# ts.net
KiCad netlist of a schematic drawn in Altium Designer
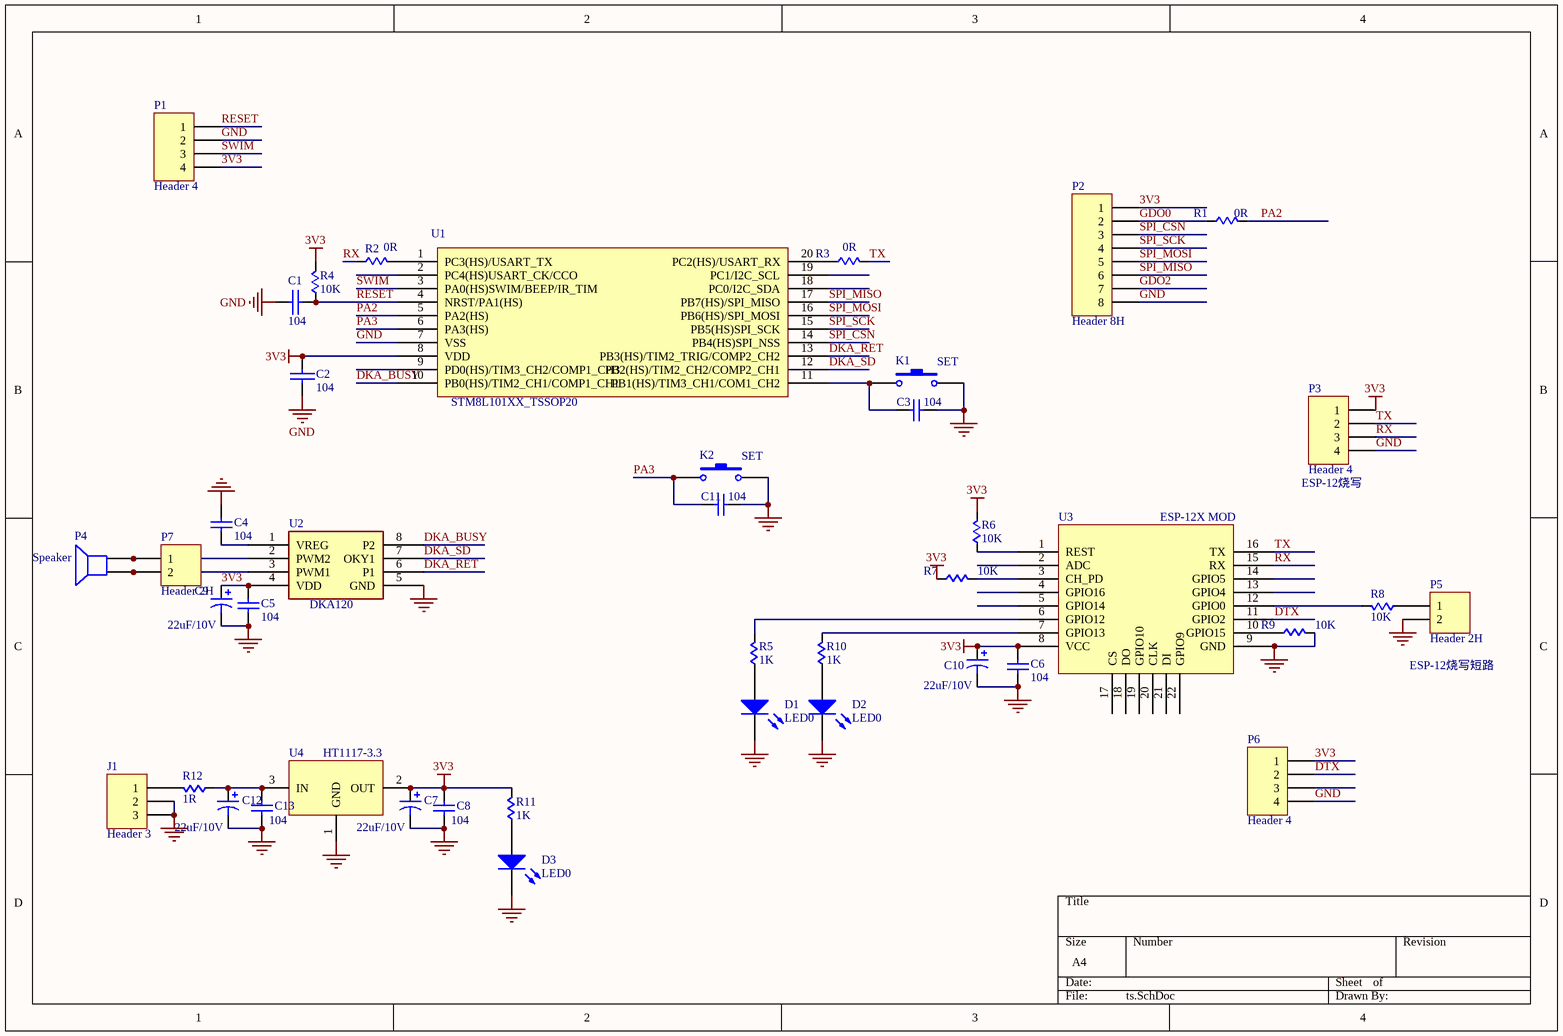
[diagram p0: ts.SchDoc]

(export (version "E")
  (design (tool "Eeschema 10.0.6"))
  (components
    (comp (ref "C1")
      (value "104")
      (footprint "0603")
      (description "Capacitor")
      (libsource (lib "*") (part "CAP"))
    )
    (comp (ref "C2")
      (value "104")
      (footprint "0603")
      (description "Capacitor")
      (libsource (lib "") (part "CAP_1"))
    )
    (comp (ref "C3")
      (value "104")
      (footprint "0603")
      (description "Capacitor (Semiconductor SIM Model)")
      (fields (field (name "PUBLISHER") "Altium Limited"))
      (libsource (lib "") (part "Cap Semi_1"))
    )
    (comp (ref "C4")
      (value "104")
      (footprint "0603")
      (description "Capacitor (Semiconductor SIM Model)")
      (fields (field (name "PUBLISHER") "Altium Limited"))
      (libsource (lib "Miscellaneous Devices") (part "Cap Semi"))
    )
    (comp (ref "C5")
      (value "104")
      (footprint "0603")
      (description "Capacitor (Semiconductor SIM Model)")
      (fields (field (name "PUBLISHER") "Altium Limited"))
      (libsource (lib "Miscellaneous Devices") (part "Cap Semi"))
    )
    (comp (ref "C6")
      (value "104")
      (footprint "0603")
      (description "Capacitor (Semiconductor SIM Model)")
      (fields (field (name "PUBLISHER") "Altium Limited"))
      (libsource (lib "Miscellaneous Devices") (part "Cap Semi"))
    )
    (comp (ref "C7")
      (value "22uF/10V")
      (footprint "T3528")
      (description "Polarized Capacitor (Surface Mount)")
      (fields (field (name "Comment") "20uF/10V") (field (name "PUBLISHER") "Altium Limited"))
      (libsource (lib "Miscellaneous Devices") (part "Cap Pol3"))
    )
    (comp (ref "C8")
      (value "104")
      (footprint "0603")
      (description "Capacitor (Semiconductor SIM Model)")
      (fields (field (name "PUBLISHER") "Altium Limited"))
      (libsource (lib "Miscellaneous Devices") (part "Cap Semi"))
    )
    (comp (ref "C9")
      (value "22uF/10V")
      (footprint "T3528")
      (description "Polarized Capacitor (Surface Mount)")
      (fields (field (name "Comment") "20uF/10V") (field (name "PUBLISHER") "Altium Limited"))
      (libsource (lib "Miscellaneous Devices") (part "Cap Pol3"))
    )
    (comp (ref "C10")
      (value "22uF/10V")
      (footprint "T3528")
      (description "Polarized Capacitor (Surface Mount)")
      (fields (field (name "Comment") "20uF/10V") (field (name "PUBLISHER") "Altium Limited"))
      (libsource (lib "Miscellaneous Devices") (part "Cap Pol3"))
    )
    (comp (ref "C11")
      (value "104")
      (footprint "0603")
      (description "Capacitor (Semiconductor SIM Model)")
      (fields (field (name "PUBLISHER") "Altium Limited"))
      (libsource (lib "") (part "Cap Semi_1"))
    )
    (comp (ref "C12")
      (value "22uF/10V")
      (footprint "T3528")
      (description "Polarized Capacitor (Surface Mount)")
      (fields (field (name "Comment") "20uF/10V") (field (name "PUBLISHER") "Altium Limited"))
      (libsource (lib "Miscellaneous Devices") (part "Cap Pol3"))
    )
    (comp (ref "C13")
      (value "104")
      (footprint "0603")
      (description "Capacitor (Semiconductor SIM Model)")
      (fields (field (name "PUBLISHER") "Altium Limited"))
      (libsource (lib "Miscellaneous Devices") (part "Cap Semi"))
    )
    (comp (ref "D1")
      (value "LED0")
      (footprint "LED2")
      (description "Typical INFRARED GaAs LED")
      (fields (field (name "PUBLISHER") "Altium Limited"))
      (libsource (lib "Miscellaneous Devices") (part "LED0"))
    )
    (comp (ref "D2")
      (value "LED0")
      (footprint "LED2")
      (description "Typical INFRARED GaAs LED")
      (fields (field (name "PUBLISHER") "Altium Limited"))
      (libsource (lib "Miscellaneous Devices") (part "LED0"))
    )
    (comp (ref "D3")
      (value "LED0")
      (footprint "LED2")
      (description "Typical INFRARED GaAs LED")
      (fields (field (name "PUBLISHER") "Altium Limited"))
      (libsource (lib "Miscellaneous Devices") (part "LED0"))
    )
    (comp (ref "J1")
      (value "Header 3")
      (footprint "DC3.5")
      (description "Header, 3-Pin")
      (fields (field (name "PUBLISHER") "Altium Limited"))
      (libsource (lib "Miscellaneous Connectors") (part "Header 3"))
    )
    (comp (ref "K1")
      (value "SET")
      (footprint "KEY_1")
      (description "Switch")
      (fields (field (name "PUBLISHER") "Altium Limited"))
      (libsource (lib "Miscellaneous Devices") (part "SW-PB"))
    )
    (comp (ref "K2")
      (value "SET")
      (footprint "KEY_1")
      (description "Switch")
      (fields (field (name "PUBLISHER") "Altium Limited"))
      (libsource (lib "Miscellaneous Devices") (part "SW-PB"))
    )
    (comp (ref "P1")
      (value "Header 4")
      (footprint "PIN4-2.0")
      (description "Header, 4-Pin")
      (fields (field (name "PUBLISHER") "Altium Limited"))
      (libsource (lib "Miscellaneous Connectors") (part "Header 4"))
    )
    (comp (ref "P2")
      (value "Header 8H")
      (footprint "PIN 1.27*8")
      (description "Header, 8-Pin, Right Angle")
      (fields (field (name "PUBLISHER") "Altium Limited"))
      (libsource (lib "Miscellaneous Connectors") (part "Header 8H"))
    )
    (comp (ref "P3")
      (value "Header 4")
      (footprint "PIN4-2.0")
      (description "Header, 4-Pin")
      (fields (field (name "PUBLISHER") "Altium Limited"))
      (libsource (lib "Miscellaneous Connectors") (part "Header 4"))
    )
    (comp (ref "P4")
      (value "Speaker")
      (footprint "J-2-50")
      (description "Loudspeaker")
      (fields (field (name "PUBLISHER") "Altium Limited"))
      (libsource (lib "Miscellaneous Devices") (part "Speaker"))
    )
    (comp (ref "P5")
      (value "Header 2H")
      (footprint "HDR1X2")
      (description "Header, 2-Pin, Right Angle")
      (fields (field (name "PUBLISHER") "Altium Limited"))
      (libsource (lib "Miscellaneous Connectors") (part "Header 2H"))
    )
    (comp (ref "P6")
      (value "Header 4")
      (footprint "PIN4-2.0")
      (description "Header, 4-Pin")
      (fields (field (name "PUBLISHER") "Altium Limited"))
      (libsource (lib "Miscellaneous Connectors") (part "Header 4"))
    )
    (comp (ref "P7")
      (value "Header 2H")
      (footprint "HDR1X2")
      (description "Header, 2-Pin, Right Angle")
      (fields (field (name "PUBLISHER") "Altium Limited"))
      (libsource (lib "Miscellaneous Connectors") (part "Header 2H"))
    )
    (comp (ref "R1") (value "0R") (footprint "0603") (libsource (lib "*") (part "RES-SM")))
    (comp (ref "R2") (value "0R") (footprint "0603") (libsource (lib "*") (part "RES-SM")))
    (comp (ref "R3") (value "0R") (footprint "0603") (libsource (lib "*") (part "RES-SM")))
    (comp (ref "R4") (value "10K") (footprint "0603") (libsource (lib "*") (part "RES-SM")))
    (comp (ref "R5") (value "1K") (footprint "0603") (libsource (lib "*") (part "RES-SM")))
    (comp (ref "R6") (value "10K") (footprint "0603") (libsource (lib "*") (part "RES-SM")))
    (comp (ref "R7") (value "10K") (footprint "0603") (libsource (lib "*") (part "RES-SM")))
    (comp (ref "R8") (value "10K") (footprint "0603") (libsource (lib "*") (part "RES-SM")))
    (comp (ref "R9") (value "10K") (footprint "0603") (libsource (lib "*") (part "RES-SM")))
    (comp (ref "R10") (value "1K") (footprint "0603") (libsource (lib "*") (part "RES-SM")))
    (comp (ref "R11") (value "1K") (footprint "0603") (libsource (lib "*") (part "RES-SM")))
    (comp (ref "R12") (value "1R") (footprint "0603") (libsource (lib "*") (part "RES-SM")))
    (comp (ref "U1")
      (value "STM8L101XX_TSSOP20")
      (footprint "SSOP20")
      (libsource (lib "*") (part "STM8L101"))
    )
    (comp (ref "U2") (value "DKA120") (footprint "SO8(SOIC)") (libsource (lib "HXY") (part "DKA120")))
    (comp (ref "U3") (value "ESP-12X MOD") (footprint "ESP12") (libsource (lib "*") (part "ESP8266 MOD")))
    (comp (ref "U4") (value "HT1117-3.3") (footprint "SOT-223") (libsource (lib "HXY") (part "HT1117-3.3")))
  )
  (nets
    (net (code "1") (name "/DKA_BUSY") (class "Default")
      (node (ref "U1") (pin "10") (pinfunction "PB0(HS)/TIM2_CH1/COMP1_CH1_10") (pintype "passive"))
      (node (ref "U2") (pin "8") (pinfunction "P2_8") (pintype "passive"))
    )
    (net (code "2") (name "/DKA_RET") (class "Default")
      (node (ref "U1") (pin "13") (pinfunction "PB3(HS)/TIM2_TRIG/COMP2_CH2_13") (pintype "passive"))
      (node (ref "U2") (pin "6") (pinfunction "P1_6") (pintype "passive"))
    )
    (net (code "3") (name "/DKA_SD") (class "Default")
      (node (ref "U1") (pin "12") (pinfunction "PB2(HS)/TIM2_CH2/COMP2_CH1_12") (pintype "passive"))
      (node (ref "U2") (pin "7") (pinfunction "OKY1_7") (pintype "passive"))
    )
    (net (code "4") (name "/DTX") (class "Default")
      (node (ref "P6") (pin "2") (pinfunction "2_2") (pintype "passive"))
      (node (ref "U3") (pin "11") (pinfunction "GPIO2_11") (pintype "passive"))
    )
    (net (code "5") (name "/GDO0") (class "Default")
      (node (ref "P2") (pin "2") (pinfunction "2_2") (pintype "passive"))
      (node (ref "R1") (pin "1") (pinfunction "1_1") (pintype "passive"))
    )
    (net (code "6") (name "/GDO2") (class "Default")
      (node (ref "P2") (pin "7") (pinfunction "7_7") (pintype "passive"))
    )
    (net (code "7") (name "/PA2") (class "Default")
      (node (ref "R1") (pin "2") (pinfunction "2_2") (pintype "passive"))
      (node (ref "U1") (pin "5") (pinfunction "PA2(HS)_5") (pintype "passive"))
    )
    (net (code "8") (name "/PA3") (class "Default")
      (node (ref "C11") (pin "2") (pinfunction "2_2") (pintype "passive"))
      (node (ref "K2") (pin "1") (pinfunction "1_1") (pintype "passive"))
      (node (ref "U1") (pin "6") (pinfunction "PA3(HS)_6") (pintype "passive"))
    )
    (net (code "9") (name "/RESET") (class "Default")
      (node (ref "C1") (pin "2") (pinfunction "2_2") (pintype "passive"))
      (node (ref "P1") (pin "1") (pinfunction "1_1") (pintype "passive"))
      (node (ref "R4") (pin "1") (pinfunction "1_1") (pintype "passive"))
      (node (ref "U1") (pin "4") (pinfunction "NRST/PA1(HS)_4") (pintype "passive"))
    )
    (net (code "10") (name "/RX") (class "Default")
      (node (ref "P3") (pin "3") (pinfunction "3_3") (pintype "passive"))
      (node (ref "R2") (pin "2") (pinfunction "2_2") (pintype "passive"))
      (node (ref "U3") (pin "15") (pinfunction "RX_15") (pintype "passive"))
    )
    (net (code "11") (name "/SPI_CSN") (class "Default")
      (node (ref "P2") (pin "3") (pinfunction "3_3") (pintype "passive"))
      (node (ref "U1") (pin "14") (pinfunction "PB4(HS)SPI_NSS_14") (pintype "passive"))
    )
    (net (code "12") (name "/SPI_MISO") (class "Default")
      (node (ref "P2") (pin "6") (pinfunction "6_6") (pintype "passive"))
      (node (ref "U1") (pin "17") (pinfunction "PB7(HS)/SPI_MISO_17") (pintype "passive"))
    )
    (net (code "13") (name "/SPI_MOSI") (class "Default")
      (node (ref "P2") (pin "5") (pinfunction "5_5") (pintype "passive"))
      (node (ref "U1") (pin "16") (pinfunction "PB6(HS)/SPI_MOSI_16") (pintype "passive"))
    )
    (net (code "14") (name "/SPI_SCK") (class "Default")
      (node (ref "P2") (pin "4") (pinfunction "4_4") (pintype "passive"))
      (node (ref "U1") (pin "15") (pinfunction "PB5(HS)SPI_SCK_15") (pintype "passive"))
    )
    (net (code "15") (name "/SWIM") (class "Default")
      (node (ref "P1") (pin "3") (pinfunction "3_3") (pintype "passive"))
      (node (ref "U1") (pin "3") (pinfunction "PA0(HS)SWIM/BEEP/IR_TIM_3") (pintype "passive"))
    )
    (net (code "16") (name "/TX") (class "Default")
      (node (ref "P3") (pin "2") (pinfunction "2_2") (pintype "passive"))
      (node (ref "R3") (pin "2") (pinfunction "2_2") (pintype "passive"))
      (node (ref "U3") (pin "16") (pinfunction "TX_16") (pintype "passive"))
    )
    (net (code "17") (name "3V3") (class "Default")
      (node (ref "C10") (pin "1") (pinfunction "1_1") (pintype "passive"))
      (node (ref "C2") (pin "2") (pinfunction "2_2") (pintype "passive"))
      (node (ref "C5") (pin "2") (pinfunction "2_2") (pintype "passive"))
      (node (ref "C6") (pin "2") (pinfunction "2_2") (pintype "passive"))
      (node (ref "C7") (pin "1") (pinfunction "1_1") (pintype "passive"))
      (node (ref "C8") (pin "1") (pinfunction "1_1") (pintype "passive"))
      (node (ref "C9") (pin "1") (pinfunction "1_1") (pintype "passive"))
      (node (ref "P1") (pin "4") (pinfunction "4_4") (pintype "passive"))
      (node (ref "P2") (pin "1") (pinfunction "1_1") (pintype "passive"))
      (node (ref "P3") (pin "1") (pinfunction "1_1") (pintype "passive"))
      (node (ref "P6") (pin "1") (pinfunction "1_1") (pintype "passive"))
      (node (ref "R11") (pin "2") (pinfunction "2_2") (pintype "passive"))
      (node (ref "R4") (pin "2") (pinfunction "2_2") (pintype "passive"))
      (node (ref "R6") (pin "2") (pinfunction "2_2") (pintype "passive"))
      (node (ref "R7") (pin "1") (pinfunction "1_1") (pintype "passive"))
      (node (ref "U1") (pin "8") (pinfunction "VDD_8") (pintype "passive"))
      (node (ref "U2") (pin "4") (pinfunction "VDD_4") (pintype "passive"))
      (node (ref "U3") (pin "8") (pinfunction "VCC_8") (pintype "passive"))
      (node (ref "U4") (pin "2") (pinfunction "OUT_2") (pintype "passive"))
    )
    (net (code "18") (name "GND") (class "Default")
      (node (ref "C1") (pin "1") (pinfunction "1_1") (pintype "passive"))
      (node (ref "C10") (pin "2") (pinfunction "2_2") (pintype "passive"))
      (node (ref "C11") (pin "1") (pinfunction "1_1") (pintype "passive"))
      (node (ref "C12") (pin "2") (pinfunction "2_2") (pintype "passive"))
      (node (ref "C13") (pin "2") (pinfunction "2_2") (pintype "passive"))
      (node (ref "C2") (pin "1") (pinfunction "1_1") (pintype "passive"))
      (node (ref "C3") (pin "1") (pinfunction "1_1") (pintype "passive"))
      (node (ref "C4") (pin "2") (pinfunction "2_2") (pintype "passive"))
      (node (ref "C5") (pin "1") (pinfunction "1_1") (pintype "passive"))
      (node (ref "C6") (pin "1") (pinfunction "1_1") (pintype "passive"))
      (node (ref "C7") (pin "2") (pinfunction "2_2") (pintype "passive"))
      (node (ref "C8") (pin "2") (pinfunction "2_2") (pintype "passive"))
      (node (ref "C9") (pin "2") (pinfunction "2_2") (pintype "passive"))
      (node (ref "D1") (pin "2") (pinfunction "K_2") (pintype "passive"))
      (node (ref "D2") (pin "2") (pinfunction "K_2") (pintype "passive"))
      (node (ref "D3") (pin "2") (pinfunction "K_2") (pintype "passive"))
      (node (ref "J1") (pin "2") (pinfunction "2_2") (pintype "passive"))
      (node (ref "J1") (pin "3") (pinfunction "3_3") (pintype "passive"))
      (node (ref "K1") (pin "2") (pinfunction "2_2") (pintype "passive"))
      (node (ref "K2") (pin "2") (pinfunction "2_2") (pintype "passive"))
      (node (ref "P1") (pin "2") (pinfunction "2_2") (pintype "passive"))
      (node (ref "P2") (pin "8") (pinfunction "8_8") (pintype "passive"))
      (node (ref "P3") (pin "4") (pinfunction "4_4") (pintype "passive"))
      (node (ref "P5") (pin "2") (pinfunction "2_2") (pintype "passive"))
      (node (ref "P6") (pin "4") (pinfunction "4_4") (pintype "passive"))
      (node (ref "R9") (pin "2") (pinfunction "2_2") (pintype "passive"))
      (node (ref "U1") (pin "7") (pinfunction "VSS_7") (pintype "passive"))
      (node (ref "U2") (pin "5") (pinfunction "GND_5") (pintype "passive"))
      (node (ref "U3") (pin "9") (pinfunction "GND_9") (pintype "passive"))
      (node (ref "U4") (pin "1") (pinfunction "GND_1") (pintype "passive"))
    )
    (net (code "19") (name "Net-(D1-A)") (class "Default")
      (node (ref "D1") (pin "1") (pinfunction "A_1") (pintype "passive"))
      (node (ref "R5") (pin "1") (pinfunction "1_1") (pintype "passive"))
    )
    (net (code "20") (name "Net-(D2-A)") (class "Default")
      (node (ref "D2") (pin "1") (pinfunction "A_1") (pintype "passive"))
      (node (ref "R10") (pin "1") (pinfunction "1_1") (pintype "passive"))
    )
    (net (code "21") (name "Net-(D3-A)") (class "Default")
      (node (ref "D3") (pin "1") (pinfunction "A_1") (pintype "passive"))
      (node (ref "R11") (pin "1") (pinfunction "1_1") (pintype "passive"))
    )
    (net (code "22") (name "Net-(J1-Pad1)") (class "Default")
      (node (ref "J1") (pin "1") (pinfunction "1_1") (pintype "passive"))
      (node (ref "R12") (pin "2") (pinfunction "2_2") (pintype "passive"))
    )
    (net (code "23") (name "Net-(P5-Pad1)") (class "Default")
      (node (ref "P5") (pin "1") (pinfunction "1_1") (pintype "passive"))
      (node (ref "R8") (pin "1") (pinfunction "1_1") (pintype "passive"))
    )
    (net (code "24") (name "Net-(U1-PB1(HS){slash}TIM3_CH1{slash}COM1_CH2)") (class "Default")
      (node (ref "C3") (pin "2") (pinfunction "2_2") (pintype "passive"))
      (node (ref "K1") (pin "1") (pinfunction "1_1") (pintype "passive"))
      (node (ref "U1") (pin "11") (pinfunction "PB1(HS)/TIM3_CH1/COM1_CH2_11") (pintype "passive"))
    )
    (net (code "25") (name "Net-(U1-PC2(HS){slash}USART_RX)") (class "Default")
      (node (ref "R3") (pin "1") (pinfunction "1_1") (pintype "passive"))
      (node (ref "U1") (pin "20") (pinfunction "PC2(HS)/USART_RX_20") (pintype "passive"))
    )
    (net (code "26") (name "Net-(U1-PC3(HS){slash}USART_TX)") (class "Default")
      (node (ref "R2") (pin "1") (pinfunction "1_1") (pintype "passive"))
      (node (ref "U1") (pin "1") (pinfunction "PC3(HS)/USART_TX_1") (pintype "passive"))
    )
    (net (code "27") (name "Net-(U2-PWM1)") (class "Default")
      (node (ref "P4") (pin "1") (pinfunction "1_1") (pintype "passive"))
      (node (ref "P7") (pin "2") (pinfunction "2_2") (pintype "passive"))
      (node (ref "U2") (pin "3") (pinfunction "PWM1_3") (pintype "passive"))
    )
    (net (code "28") (name "Net-(U2-PWM2)") (class "Default")
      (node (ref "P4") (pin "2") (pinfunction "2_2") (pintype "passive"))
      (node (ref "P7") (pin "1") (pinfunction "1_1") (pintype "passive"))
      (node (ref "U2") (pin "2") (pinfunction "PWM2_2") (pintype "passive"))
    )
    (net (code "29") (name "Net-(U2-VREG)") (class "Default")
      (node (ref "C4") (pin "1") (pinfunction "1_1") (pintype "passive"))
      (node (ref "U2") (pin "1") (pinfunction "VREG_1") (pintype "passive"))
    )
    (net (code "30") (name "Net-(U3-CH_PD)") (class "Default")
      (node (ref "R7") (pin "2") (pinfunction "2_2") (pintype "passive"))
      (node (ref "U3") (pin "3") (pinfunction "CH_PD_3") (pintype "passive"))
    )
    (net (code "31") (name "Net-(U3-GPIO0)") (class "Default")
      (node (ref "R8") (pin "2") (pinfunction "2_2") (pintype "passive"))
      (node (ref "U3") (pin "12") (pinfunction "GPIO0_12") (pintype "passive"))
    )
    (net (code "32") (name "Net-(U3-GPIO12)") (class "Default")
      (node (ref "R5") (pin "2") (pinfunction "2_2") (pintype "passive"))
      (node (ref "U3") (pin "6") (pinfunction "GPIO12_6") (pintype "passive"))
    )
    (net (code "33") (name "Net-(U3-GPIO13)") (class "Default")
      (node (ref "R10") (pin "2") (pinfunction "2_2") (pintype "passive"))
      (node (ref "U3") (pin "7") (pinfunction "GPIO13_7") (pintype "passive"))
    )
    (net (code "34") (name "Net-(U3-GPIO15)") (class "Default")
      (node (ref "R9") (pin "1") (pinfunction "1_1") (pintype "passive"))
      (node (ref "U3") (pin "10") (pinfunction "GPIO15_10") (pintype "passive"))
    )
    (net (code "35") (name "Net-(U3-REST)") (class "Default")
      (node (ref "R6") (pin "1") (pinfunction "1_1") (pintype "passive"))
      (node (ref "U3") (pin "1") (pinfunction "REST_1") (pintype "passive"))
    )
    (net (code "36") (name "Net-(U4-IN)") (class "Default")
      (node (ref "C12") (pin "1") (pinfunction "1_1") (pintype "passive"))
      (node (ref "C13") (pin "1") (pinfunction "1_1") (pintype "passive"))
      (node (ref "R12") (pin "1") (pinfunction "1_1") (pintype "passive"))
      (node (ref "U4") (pin "3") (pinfunction "IN_3") (pintype "passive"))
    )
    (net (code "37") (name "unconnected-(P6-Pad3)") (class "Default")
      (node (ref "P6") (pin "3") (pinfunction "3_3") (pintype "passive"))
    )
    (net (code "38") (name "unconnected-(U1-PC0{slash}I2C_SDA-Pad18)") (class "Default")
      (node (ref "U1") (pin "18") (pinfunction "PC0/I2C_SDA_18") (pintype "passive"))
    )
    (net (code "39") (name "unconnected-(U1-PC1{slash}I2C_SCL-Pad19)") (class "Default")
      (node (ref "U1") (pin "19") (pinfunction "PC1/I2C_SCL_19") (pintype "passive"))
    )
    (net (code "40") (name "unconnected-(U1-PC4(HS)USART_CK{slash}CCO-Pad2)") (class "Default")
      (node (ref "U1") (pin "2") (pinfunction "PC4(HS)USART_CK/CCO_2") (pintype "passive"))
    )
    (net (code "41") (name "unconnected-(U1-PD0(HS){slash}TIM3_CH2{slash}COMP1_CH3-Pad9)") (class "Default")
      (node (ref "U1") (pin "9") (pinfunction "PD0(HS)/TIM3_CH2/COMP1_CH3_9") (pintype "passive"))
    )
    (net (code "42") (name "unconnected-(U3-ADC-Pad2)") (class "Default")
      (node (ref "U3") (pin "2") (pinfunction "ADC_2") (pintype "passive"))
    )
    (net (code "43") (name "unconnected-(U3-CLK-Pad20)") (class "Default")
      (node (ref "U3") (pin "20") (pinfunction "CLK_20") (pintype "passive"))
    )
    (net (code "44") (name "unconnected-(U3-CS-Pad17)") (class "Default")
      (node (ref "U3") (pin "17") (pinfunction "CS_17") (pintype "passive"))
    )
    (net (code "45") (name "unconnected-(U3-DI-Pad21)") (class "Default")
      (node (ref "U3") (pin "21") (pinfunction "DI_21") (pintype "passive"))
    )
    (net (code "46") (name "unconnected-(U3-DO-Pad18)") (class "Default")
      (node (ref "U3") (pin "18") (pinfunction "DO_18") (pintype "passive"))
    )
    (net (code "47") (name "unconnected-(U3-GPIO4-Pad13)") (class "Default")
      (node (ref "U3") (pin "13") (pinfunction "GPIO4_13") (pintype "passive"))
    )
    (net (code "48") (name "unconnected-(U3-GPIO5-Pad14)") (class "Default")
      (node (ref "U3") (pin "14") (pinfunction "GPIO5_14") (pintype "passive"))
    )
    (net (code "49") (name "unconnected-(U3-GPIO9-Pad22)") (class "Default")
      (node (ref "U3") (pin "22") (pinfunction "GPIO9_22") (pintype "passive"))
    )
    (net (code "50") (name "unconnected-(U3-GPIO10-Pad19)") (class "Default")
      (node (ref "U3") (pin "19") (pinfunction "GPIO10_19") (pintype "passive"))
    )
    (net (code "51") (name "unconnected-(U3-GPIO14-Pad5)") (class "Default")
      (node (ref "U3") (pin "5") (pinfunction "GPIO14_5") (pintype "passive"))
    )
    (net (code "52") (name "unconnected-(U3-GPIO16-Pad4)") (class "Default")
      (node (ref "U3") (pin "4") (pinfunction "GPIO16_4") (pintype "passive"))
    )
  )
)
